# house_interior_board.net
KiCad netlist of a schematic drawn in EAGLE
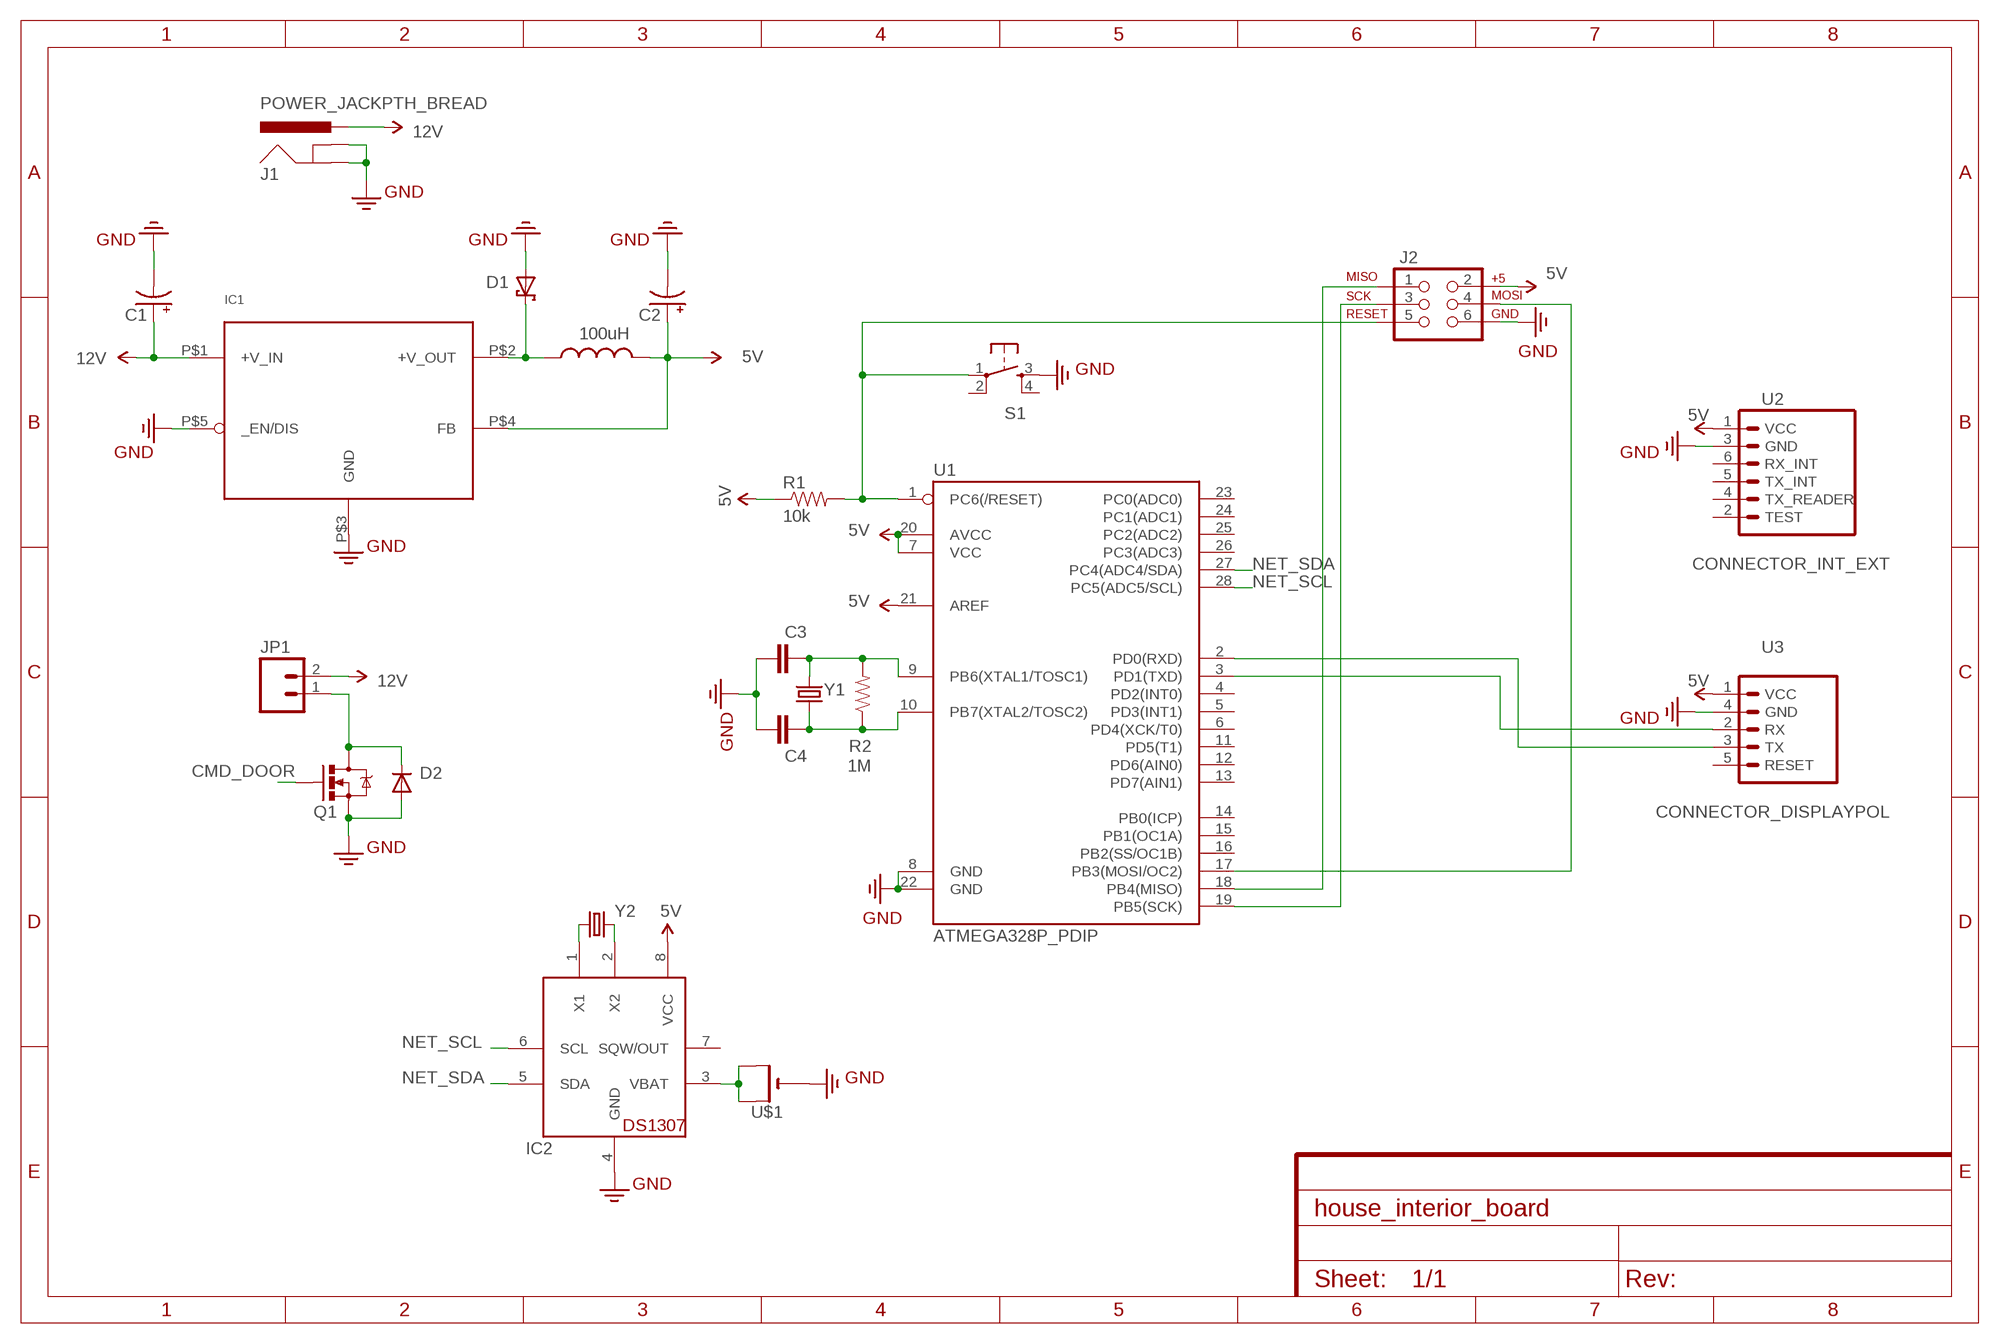
[diagram p0: schematic, sheet 1]

(export (version "E")
  (design (tool "Eeschema 10.0.6"))
  (components
    (comp (ref "C1")
      (value "100UF-25V-20%(PTH)")
      (footprint "eagle-import:CPOL-RADIAL-100UF-25V")
      (libsource (lib "eagle-import") (part "100UF-25V-20%(PTH)"))
    )
    (comp (ref "C2")
      (value "CAP-09538")
      (footprint "eagle-import:CPOL-RADIAL-1000UF-25V")
      (libsource (lib "eagle-import") (part "1000UF-25V(PTH)"))
    )
    (comp (ref "C3")
      (value "22PF-50VPTH")
      (footprint "eagle-import:CAP-PTH-SMALL")
      (libsource (lib "eagle-import") (part "22PF-50VPTH"))
    )
    (comp (ref "C4")
      (value "22PF-50VPTH")
      (footprint "eagle-import:CAP-PTH-SMALL")
      (libsource (lib "eagle-import") (part "22PF-50VPTH"))
    )
    (comp (ref "D1")
      (value "1N5822PTH")
      (footprint "eagle-import:DO201T15")
      (libsource (lib "eagle-import") (part "1N5822PTH"))
    )
    (comp (ref "D2")
      (value "1N4004")
      (footprint "eagle-import:DO41-10")
      (libsource (lib "eagle-import") (part "1N4004"))
    )
    (comp (ref "IC1")
      (value "LM2576-T05A")
      (footprint "eagle-import:TO-220-5_IN-LINE")
      (libsource (lib "eagle-import") (part "LM2576-T05A"))
    )
    (comp (ref "IC2")
      (value "DS1307")
      (footprint "eagle-import:DIL08")
      (libsource (lib "eagle-import") (part "DS1307"))
    )
    (comp (ref "J1")
      (value "POWER_JACKPTH_BREAD")
      (footprint "eagle-import:POWER_JACK_PTH_BREAD")
      (libsource (lib "eagle-import") (part "POWER_JACKPTH_BREAD"))
    )
    (comp (ref "J2")
      (value "AVR_SPI_PRG_6PTH")
      (footprint "eagle-import:2X3")
      (libsource (lib "eagle-import") (part "AVR_SPI_PRG_6PTH"))
    )
    (comp (ref "JP1")
      (value "M02JST-PTH-VERT")
      (footprint "eagle-import:JST-2-PTH-VERT")
      (libsource (lib "eagle-import") (part "M02JST-PTH-VERT"))
    )
    (comp (ref "L1")
      (value "100uH")
      (footprint "eagle-import:RLB0912")
      (libsource (lib "eagle-import") (part "INDUCTORRLB0912"))
    )
    (comp (ref "Q1")
      (value "MOSFET-NCHANNELFQP30N06L")
      (footprint "eagle-import:TO220V")
      (libsource (lib "eagle-import") (part "MOSFET-NCHANNELFQP30N06L"))
    )
    (comp (ref "R1")
      (value "10k")
      (footprint "eagle-import:AXIAL-0.3")
      (libsource (lib "eagle-import") (part "10KOHM-1/4W-1%(PTH)HORIZ"))
    )
    (comp (ref "R2")
      (value "1M")
      (footprint "eagle-import:AXIAL-0.3")
      (libsource (lib "eagle-import") (part "1MOHM1/10W1%(0603)HON"))
    )
    (comp (ref "S1")
      (value "TAC_SWITCHPTH")
      (footprint "eagle-import:TACTILE-PTH")
      (libsource (lib "eagle-import") (part "TAC_SWITCHPTH"))
    )
    (comp (ref "U$1")
      (value "CR1220THM")
      (footprint "eagle-import:CR1220-THM")
      (libsource (lib "eagle-import") (part "CR1220THM"))
    )
    (comp (ref "U1")
      (value "ATMEGA328P_PDIP")
      (footprint "eagle-import:DIL28-3")
      (libsource (lib "eagle-import") (part "ATMEGA328P_PDIP"))
    )
    (comp (ref "U2")
      (value "CONNECTOR_INT_EXT")
      (footprint "eagle-import:1X06_COMMON")
      (libsource (lib "eagle-import") (part "CONNECTOR_INT_EXT"))
    )
    (comp (ref "U3")
      (value "CONNECTOR_DISPLAYPOL")
      (footprint "eagle-import:1X05_POL")
      (libsource (lib "eagle-import") (part "CONNECTOR_DISPLAYPOL"))
    )
    (comp (ref "Y1")
      (value "CRYSTALHC49US")
      (footprint "eagle-import:HC49US")
      (libsource (lib "eagle-import") (part "CRYSTALHC49US"))
    )
    (comp (ref "Y2")
      (value "CRYSTALTC26H")
      (footprint "eagle-import:TC26H")
      (libsource (lib "eagle-import") (part "CRYSTALTC26H"))
    )
  )
  (nets
    (net (code "1") (name "/CMD_DOOR") (class "Default")
      (node (ref "Q1") (pin "1") (pinfunction "G_1") (pintype "passive"))
    )
    (net (code "2") (name "/NET_SCL") (class "Default")
      (node (ref "IC2") (pin "6") (pinfunction "SCL_6") (pintype "bidirectional"))
      (node (ref "U1") (pin "28") (pinfunction "PC5(ADC5/SCL)_28") (pintype "bidirectional"))
    )
    (net (code "3") (name "/NET_SDA") (class "Default")
      (node (ref "IC2") (pin "5") (pinfunction "SDA_5") (pintype "bidirectional"))
      (node (ref "U1") (pin "27") (pinfunction "PC4(ADC4/SDA)_27") (pintype "bidirectional"))
    )
    (net (code "4") (name "5V") (class "Default")
      (node (ref "C2") (pin "+") (pinfunction "+_+") (pintype "passive"))
      (node (ref "IC1") (pin "P$4") (pinfunction "FB_P$4") (pintype "input"))
      (node (ref "IC2") (pin "8") (pinfunction "VCC_8") (pintype "power_in"))
      (node (ref "J2") (pin "2") (pinfunction "2_2") (pintype "passive"))
      (node (ref "L1") (pin "2") (pinfunction "2_2") (pintype "passive"))
      (node (ref "R1") (pin "P$1") (pinfunction "1_P$1") (pintype "passive"))
      (node (ref "U1") (pin "20") (pinfunction "AVCC_20") (pintype "bidirectional"))
      (node (ref "U1") (pin "21") (pinfunction "AREF_21") (pintype "bidirectional"))
      (node (ref "U1") (pin "7") (pinfunction "VCC_7") (pintype "bidirectional"))
      (node (ref "U2") (pin "1") (pinfunction "VCC_1") (pintype "passive"))
      (node (ref "U3") (pin "1") (pinfunction "VCC_1") (pintype "passive"))
    )
    (net (code "5") (name "12V") (class "Default")
      (node (ref "C1") (pin "1") (pinfunction "+_1") (pintype "passive"))
      (node (ref "IC1") (pin "P$1") (pinfunction "+V_IN_P$1") (pintype "input"))
      (node (ref "J1") (pin "PWR") (pinfunction "PWR_PWR") (pintype "bidirectional"))
      (node (ref "JP1") (pin "2") (pinfunction "2_2") (pintype "passive"))
    )
    (net (code "6") (name "GND") (class "Default")
      (node (ref "C1") (pin "2") (pinfunction "-_2") (pintype "passive"))
      (node (ref "C2") (pin "-") (pinfunction "-_-") (pintype "passive"))
      (node (ref "C3") (pin "2") (pinfunction "2_2") (pintype "passive"))
      (node (ref "C4") (pin "2") (pinfunction "2_2") (pintype "passive"))
      (node (ref "D1") (pin "A") (pinfunction "A_A") (pintype "passive"))
      (node (ref "D2") (pin "A") (pinfunction "A_A") (pintype "passive"))
      (node (ref "IC1") (pin "P$3") (pinfunction "GND_P$3") (pintype "power_in"))
      (node (ref "IC1") (pin "P$5") (pinfunction "_EN/DIS_P$5") (pintype "input"))
      (node (ref "IC2") (pin "4") (pinfunction "GND_4") (pintype "power_in"))
      (node (ref "J1") (pin "GND") (pinfunction "GND_GND") (pintype "bidirectional"))
      (node (ref "J1") (pin "GNDBREAK") (pinfunction "GNDBREAK_GNDBREAK") (pintype "bidirectional"))
      (node (ref "J2") (pin "6") (pinfunction "6_6") (pintype "passive"))
      (node (ref "Q1") (pin "3") (pinfunction "S_3") (pintype "passive"))
      (node (ref "S1") (pin "3") (pinfunction "3_3") (pintype "passive"))
      (node (ref "U$1") (pin "-") (pinfunction "-_-") (pintype "passive"))
      (node (ref "U1") (pin "22") (pinfunction "GND_22") (pintype "bidirectional"))
      (node (ref "U1") (pin "8") (pinfunction "GND_8") (pintype "bidirectional"))
      (node (ref "U2") (pin "3") (pinfunction "GND_3") (pintype "passive"))
      (node (ref "U3") (pin "4") (pinfunction "GND_4") (pintype "passive"))
    )
    (net (code "7") (name "Net-(IC1-+V_OUT)") (class "Default")
      (node (ref "D1") (pin "C") (pinfunction "C_C") (pintype "passive"))
      (node (ref "IC1") (pin "P$2") (pinfunction "+V_OUT_P$2") (pintype "output"))
      (node (ref "L1") (pin "1") (pinfunction "1_1") (pintype "passive"))
    )
    (net (code "8") (name "Net-(IC2-VBAT)") (class "Default")
      (node (ref "IC2") (pin "3") (pinfunction "VBAT_3") (pintype "power_in"))
      (node (ref "U$1") (pin "+1") (pinfunction "+_+1") (pintype "passive"))
      (node (ref "U$1") (pin "+2") (pinfunction "+1_+2") (pintype "passive"))
    )
    (net (code "9") (name "Net-(IC2-X1)") (class "Default")
      (node (ref "IC2") (pin "1") (pinfunction "X1_1") (pintype "passive"))
      (node (ref "Y2") (pin "1") (pinfunction "1_1") (pintype "passive"))
    )
    (net (code "10") (name "Net-(IC2-X2)") (class "Default")
      (node (ref "IC2") (pin "2") (pinfunction "X2_2") (pintype "passive"))
      (node (ref "Y2") (pin "2") (pinfunction "2_2") (pintype "passive"))
    )
    (net (code "11") (name "Net-(Q1-D)") (class "Default")
      (node (ref "D2") (pin "C") (pinfunction "C_C") (pintype "passive"))
      (node (ref "JP1") (pin "1") (pinfunction "1_1") (pintype "passive"))
      (node (ref "Q1") (pin "2") (pinfunction "D_2") (pintype "passive"))
    )
    (net (code "12") (name "Net-(R1-2)") (class "Default")
      (node (ref "J2") (pin "5") (pinfunction "5_5") (pintype "passive"))
      (node (ref "R1") (pin "P$2") (pinfunction "2_P$2") (pintype "passive"))
      (node (ref "S1") (pin "1") (pinfunction "1_1") (pintype "passive"))
      (node (ref "U1") (pin "1") (pinfunction "PC6(/RESET)_1") (pintype "bidirectional"))
    )
    (net (code "13") (name "Net-(R2-1)") (class "Default")
      (node (ref "C4") (pin "1") (pinfunction "1_1") (pintype "passive"))
      (node (ref "R2") (pin "P$1") (pinfunction "1_P$1") (pintype "passive"))
      (node (ref "U1") (pin "10") (pinfunction "PB7(XTAL2/TOSC2)_10") (pintype "bidirectional"))
      (node (ref "Y1") (pin "1") (pinfunction "1_1") (pintype "passive"))
    )
    (net (code "14") (name "Net-(R2-2)") (class "Default")
      (node (ref "C3") (pin "1") (pinfunction "1_1") (pintype "passive"))
      (node (ref "R2") (pin "P$2") (pinfunction "2_P$2") (pintype "passive"))
      (node (ref "U1") (pin "9") (pinfunction "PB6(XTAL1/TOSC1)_9") (pintype "bidirectional"))
      (node (ref "Y1") (pin "2") (pinfunction "2_2") (pintype "passive"))
    )
    (net (code "15") (name "Net-(U1-PB3(MOSI{slash}OC2))") (class "Default")
      (node (ref "J2") (pin "4") (pinfunction "4_4") (pintype "passive"))
      (node (ref "U1") (pin "17") (pinfunction "PB3(MOSI/OC2)_17") (pintype "bidirectional"))
    )
    (net (code "16") (name "Net-(U1-PB4(MISO))") (class "Default")
      (node (ref "J2") (pin "1") (pinfunction "1_1") (pintype "passive"))
      (node (ref "U1") (pin "18") (pinfunction "PB4(MISO)_18") (pintype "bidirectional"))
    )
    (net (code "17") (name "Net-(U1-PB5(SCK))") (class "Default")
      (node (ref "J2") (pin "3") (pinfunction "3_3") (pintype "passive"))
      (node (ref "U1") (pin "19") (pinfunction "PB5(SCK)_19") (pintype "bidirectional"))
    )
    (net (code "18") (name "Net-(U1-PD0(RXD))") (class "Default")
      (node (ref "U1") (pin "2") (pinfunction "PD0(RXD)_2") (pintype "bidirectional"))
      (node (ref "U3") (pin "3") (pinfunction "TX_3") (pintype "passive"))
    )
    (net (code "19") (name "Net-(U1-PD1(TXD))") (class "Default")
      (node (ref "U1") (pin "3") (pinfunction "PD1(TXD)_3") (pintype "bidirectional"))
      (node (ref "U3") (pin "2") (pinfunction "RX_2") (pintype "passive"))
    )
    (net (code "20") (name "unconnected-(IC2-SQW{slash}OUT-Pad7)") (class "Default")
      (node (ref "IC2") (pin "7") (pinfunction "SQW/OUT_7") (pintype "bidirectional"))
    )
    (net (code "21") (name "unconnected-(S1-Pad2)") (class "Default")
      (node (ref "S1") (pin "2") (pinfunction "2_2") (pintype "passive"))
    )
    (net (code "22") (name "unconnected-(S1-Pad4)") (class "Default")
      (node (ref "S1") (pin "4") (pinfunction "4_4") (pintype "passive"))
    )
    (net (code "23") (name "unconnected-(U1-PB0(ICP)-Pad14)") (class "Default")
      (node (ref "U1") (pin "14") (pinfunction "PB0(ICP)_14") (pintype "bidirectional"))
    )
    (net (code "24") (name "unconnected-(U1-PB1(OC1A)-Pad15)") (class "Default")
      (node (ref "U1") (pin "15") (pinfunction "PB1(OC1A)_15") (pintype "bidirectional"))
    )
    (net (code "25") (name "unconnected-(U1-PB2(SS{slash}OC1B)-Pad16)") (class "Default")
      (node (ref "U1") (pin "16") (pinfunction "PB2(SS/OC1B)_16") (pintype "bidirectional"))
    )
    (net (code "26") (name "unconnected-(U1-PC0(ADC0)-Pad23)") (class "Default")
      (node (ref "U1") (pin "23") (pinfunction "PC0(ADC0)_23") (pintype "bidirectional"))
    )
    (net (code "27") (name "unconnected-(U1-PC1(ADC1)-Pad24)") (class "Default")
      (node (ref "U1") (pin "24") (pinfunction "PC1(ADC1)_24") (pintype "bidirectional"))
    )
    (net (code "28") (name "unconnected-(U1-PC2(ADC2)-Pad25)") (class "Default")
      (node (ref "U1") (pin "25") (pinfunction "PC2(ADC2)_25") (pintype "bidirectional"))
    )
    (net (code "29") (name "unconnected-(U1-PC3(ADC3)-Pad26)") (class "Default")
      (node (ref "U1") (pin "26") (pinfunction "PC3(ADC3)_26") (pintype "bidirectional"))
    )
    (net (code "30") (name "unconnected-(U1-PD2(INT0)-Pad4)") (class "Default")
      (node (ref "U1") (pin "4") (pinfunction "PD2(INT0)_4") (pintype "bidirectional"))
    )
    (net (code "31") (name "unconnected-(U1-PD3(INT1)-Pad5)") (class "Default")
      (node (ref "U1") (pin "5") (pinfunction "PD3(INT1)_5") (pintype "bidirectional"))
    )
    (net (code "32") (name "unconnected-(U1-PD4(XCK{slash}T0)-Pad6)") (class "Default")
      (node (ref "U1") (pin "6") (pinfunction "PD4(XCK/T0)_6") (pintype "bidirectional"))
    )
    (net (code "33") (name "unconnected-(U1-PD5(T1)-Pad11)") (class "Default")
      (node (ref "U1") (pin "11") (pinfunction "PD5(T1)_11") (pintype "bidirectional"))
    )
    (net (code "34") (name "unconnected-(U1-PD6(AIN0)-Pad12)") (class "Default")
      (node (ref "U1") (pin "12") (pinfunction "PD6(AIN0)_12") (pintype "bidirectional"))
    )
    (net (code "35") (name "unconnected-(U1-PD7(AIN1)-Pad13)") (class "Default")
      (node (ref "U1") (pin "13") (pinfunction "PD7(AIN1)_13") (pintype "bidirectional"))
    )
    (net (code "36") (name "unconnected-(U2-RX_INT-Pad6)") (class "Default")
      (node (ref "U2") (pin "6") (pinfunction "RX_INT_6") (pintype "passive"))
    )
    (net (code "37") (name "unconnected-(U2-TEST-Pad2)") (class "Default")
      (node (ref "U2") (pin "2") (pinfunction "TEST_2") (pintype "passive"))
    )
    (net (code "38") (name "unconnected-(U2-TX_INT-Pad5)") (class "Default")
      (node (ref "U2") (pin "5") (pinfunction "TX_INT_5") (pintype "passive"))
    )
    (net (code "39") (name "unconnected-(U2-TX_READER-Pad4)") (class "Default")
      (node (ref "U2") (pin "4") (pinfunction "TX_READER_4") (pintype "passive"))
    )
    (net (code "40") (name "unconnected-(U3-RESET-Pad5)") (class "Default")
      (node (ref "U3") (pin "5") (pinfunction "RESET_5") (pintype "passive"))
    )
  )
)
